# AURELIA_ALIKA.net
KiCad netlist of a schematic drawn in EAGLE
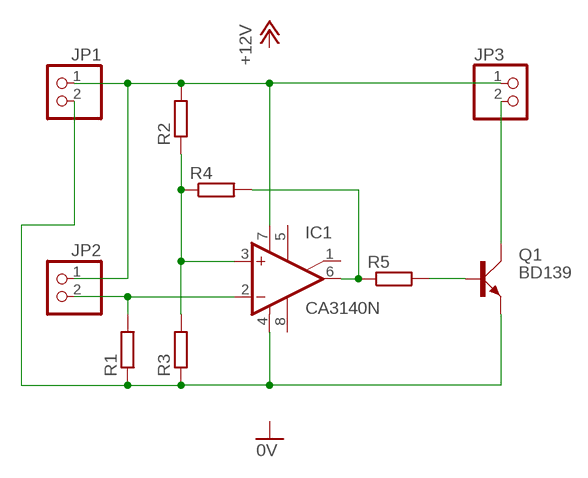
[diagram p0: schematic, sheet 1]

(export (version "E")
  (design (tool "Eeschema 10.0.6"))
  (components
    (comp (ref "IC1")
      (value "CA3140N")
      (footprint "eagle-import:DIL08")
      (libsource (lib "eagle-import") (part "CA3140N"))
    )
    (comp (ref "JP1")
      (value "PINHD-1X2")
      (footprint "eagle-import:1X02")
      (libsource (lib "eagle-import") (part "PINHD-1X2"))
    )
    (comp (ref "JP2")
      (value "PINHD-1X2")
      (footprint "eagle-import:1X02")
      (libsource (lib "eagle-import") (part "PINHD-1X2"))
    )
    (comp (ref "JP3")
      (value "PINHD-1X2")
      (footprint "eagle-import:1X02")
      (libsource (lib "eagle-import") (part "PINHD-1X2"))
    )
    (comp (ref "Q1")
      (value "BD139")
      (footprint "eagle-import:TO126AV")
      (libsource (lib "eagle-import") (part "BD139"))
    )
    (comp (ref "R1")
      (value "R-EU_0207/15")
      (footprint "eagle-import:0207_15")
      (libsource (lib "eagle-import") (part "R-EU_0207/15"))
    )
    (comp (ref "R2")
      (value "R-EU_0207/15")
      (footprint "eagle-import:0207_15")
      (libsource (lib "eagle-import") (part "R-EU_0207/15"))
    )
    (comp (ref "R3")
      (value "R-EU_0207/15")
      (footprint "eagle-import:0207_15")
      (libsource (lib "eagle-import") (part "R-EU_0207/15"))
    )
    (comp (ref "R4")
      (value "R-EU_0207/15")
      (footprint "eagle-import:0207_15")
      (libsource (lib "eagle-import") (part "R-EU_0207/15"))
    )
    (comp (ref "R5")
      (value "R-EU_0207/15")
      (footprint "eagle-import:0207_15")
      (libsource (lib "eagle-import") (part "R-EU_0207/15"))
    )
  )
  (nets
    (net (code "3") (name "Net-(IC1-+IN)") (class "Default")
      (node (ref "IC1") (pin "3") (pinfunction "+IN_3") (pintype "input"))
      (node (ref "R2") (pin "1") (pinfunction "1_1") (pintype "passive"))
      (node (ref "R3") (pin "2") (pinfunction "2_2") (pintype "passive"))
      (node (ref "R4") (pin "1") (pinfunction "1_1") (pintype "passive"))
    )
    (net (code "4") (name "Net-(IC1--IN)") (class "Default")
      (node (ref "IC1") (pin "2") (pinfunction "-IN_2") (pintype "input"))
      (node (ref "JP2") (pin "2") (pinfunction "2_2") (pintype "passive"))
      (node (ref "R1") (pin "2") (pinfunction "2_2") (pintype "passive"))
    )
    (net (code "5") (name "Net-(IC1-OUT)") (class "Default")
      (node (ref "IC1") (pin "6") (pinfunction "OUT_6") (pintype "output"))
      (node (ref "R4") (pin "2") (pinfunction "2_2") (pintype "passive"))
      (node (ref "R5") (pin "1") (pinfunction "1_1") (pintype "passive"))
    )
    (net (code "6") (name "Net-(IC1-V+)") (class "Default")
      (node (ref "IC1") (pin "7") (pinfunction "V+_7") (pintype "power_in"))
      (node (ref "JP1") (pin "1") (pinfunction "1_1") (pintype "passive"))
      (node (ref "JP2") (pin "1") (pinfunction "1_1") (pintype "passive"))
      (node (ref "JP3") (pin "1") (pinfunction "1_1") (pintype "passive"))
      (node (ref "R2") (pin "2") (pinfunction "2_2") (pintype "passive"))
    )
    (net (code "7") (name "Net-(IC1-V-)") (class "Default")
      (node (ref "IC1") (pin "4") (pinfunction "V-_4") (pintype "power_in"))
      (node (ref "JP1") (pin "2") (pinfunction "2_2") (pintype "passive"))
      (node (ref "Q1") (pin "E") (pinfunction "E_E") (pintype "passive"))
      (node (ref "R1") (pin "1") (pinfunction "1_1") (pintype "passive"))
      (node (ref "R3") (pin "1") (pinfunction "1_1") (pintype "passive"))
    )
    (net (code "8") (name "Net-(JP3-Pad2)") (class "Default")
      (node (ref "JP3") (pin "2") (pinfunction "2_2") (pintype "passive"))
      (node (ref "Q1") (pin "C") (pinfunction "C_C") (pintype "passive"))
    )
    (net (code "9") (name "Net-(Q1-PadB)") (class "Default")
      (node (ref "Q1") (pin "B") (pinfunction "B_B") (pintype "passive"))
      (node (ref "R5") (pin "2") (pinfunction "2_2") (pintype "passive"))
    )
    (net (code "10") (name "unconnected-(IC1-CMP-Pad8)") (class "Default")
      (node (ref "IC1") (pin "8") (pinfunction "CMP_8") (pintype "passive"))
    )
    (net (code "11") (name "unconnected-(IC1-ON-Pad5)") (class "Default")
      (node (ref "IC1") (pin "5") (pinfunction "ON_5") (pintype "passive"))
    )
    (net (code "12") (name "unconnected-(IC1-ON{slash}CMP-Pad1)") (class "Default")
      (node (ref "IC1") (pin "1") (pinfunction "ON/CMP_1") (pintype "passive"))
    )
  )
)
